# custom_line_V1_mux4.net
KiCad netlist of a schematic drawn in Altium Designer
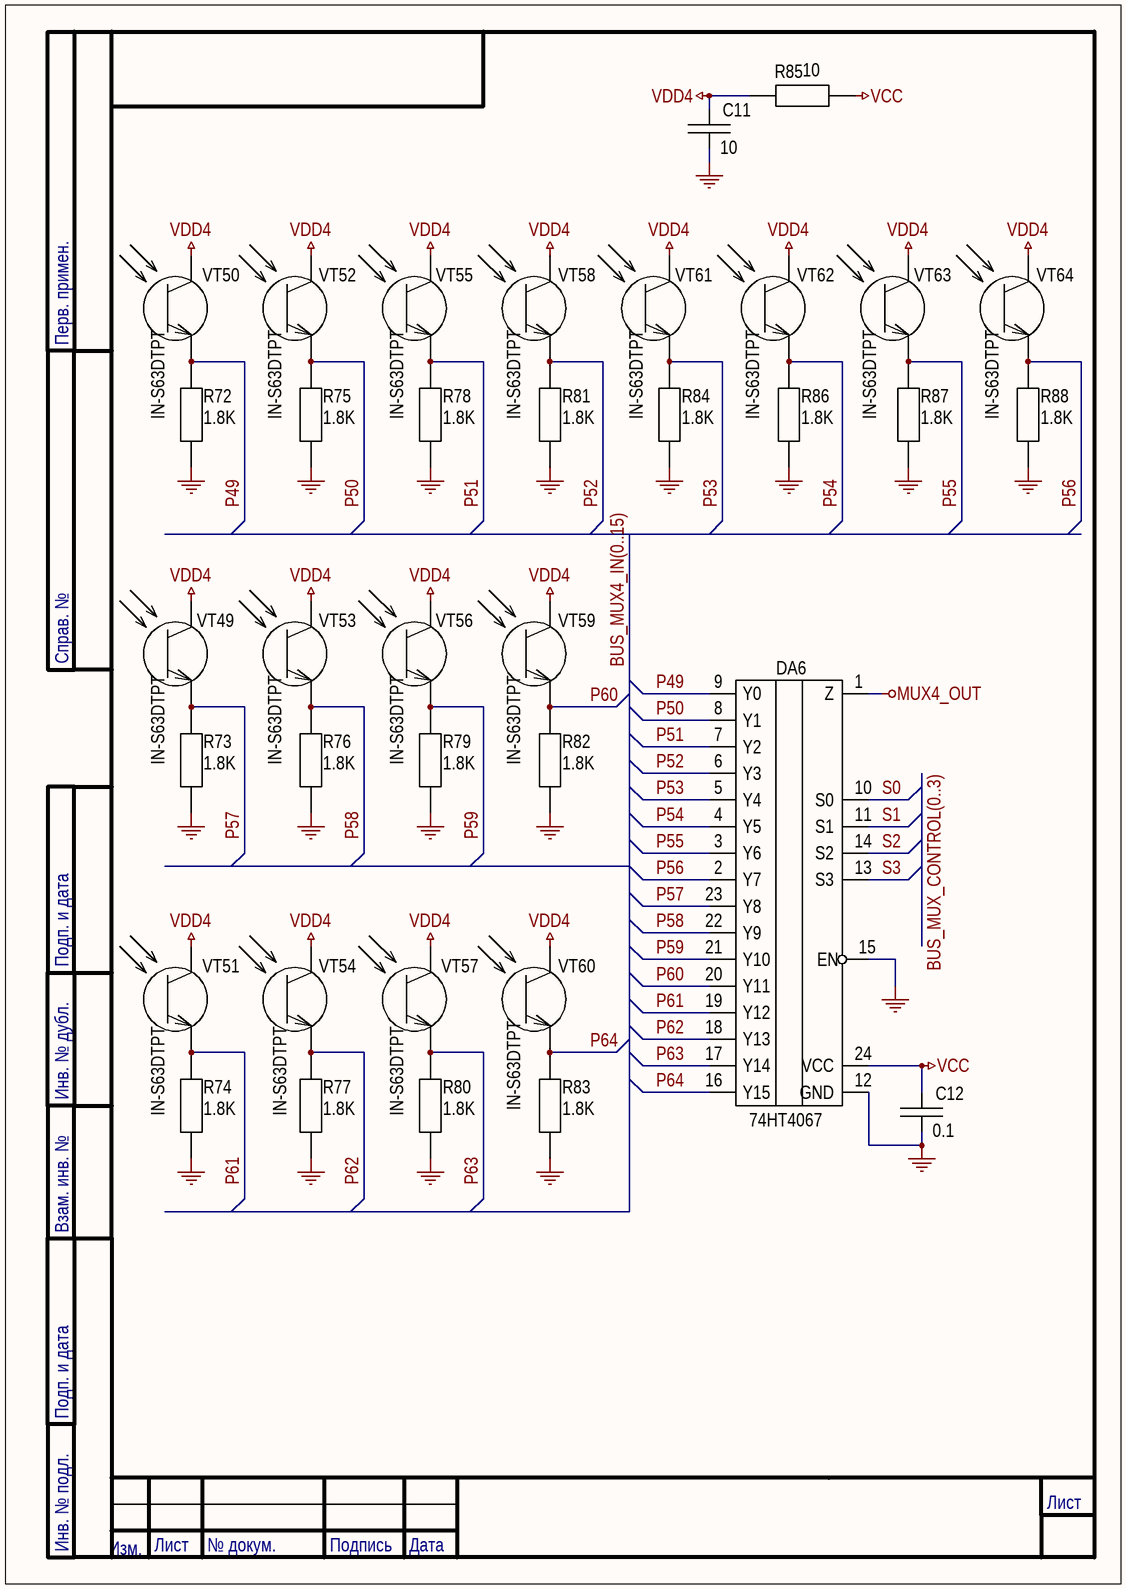
[diagram p0: custom_line_V1_mux4.SchDoc]

(export (version "E")
  (design (tool "Eeschema 10.0.6"))
  (components
    (comp (ref "C11") (value "10") (footprint "CC_0805") (libsource (lib "my_discrete_new") (part "C")))
    (comp (ref "C12") (value "0.1") (footprint "CC_0603") (libsource (lib "my_discrete_new") (part "C")))
    (comp (ref "DA6")
      (value "74HC4067")
      (footprint "TSSOP-24")
      (description "74HC4067PW")
      (fields (field (name "TYPE") "74HT4067"))
      (libsource (lib "my_microschems_new") (part "74HCT4067"))
    )
    (comp (ref "R72")
      (value "1.8K")
      (footprint "RC_0603_SMALL")
      (fields (field (name "POWER") "0.125W"))
      (libsource (lib "my_discrete_new") (part "R"))
    )
    (comp (ref "R73")
      (value "1.8K")
      (footprint "RC_0603_SMALL")
      (fields (field (name "POWER") "0.125W"))
      (libsource (lib "my_discrete_new") (part "R"))
    )
    (comp (ref "R74")
      (value "1.8K")
      (footprint "RC_0603_SMALL")
      (fields (field (name "POWER") "0.125W"))
      (libsource (lib "my_discrete_new") (part "R"))
    )
    (comp (ref "R75")
      (value "1.8K")
      (footprint "RC_0603_SMALL")
      (fields (field (name "POWER") "0.125W"))
      (libsource (lib "my_discrete_new") (part "R"))
    )
    (comp (ref "R76")
      (value "1.8K")
      (footprint "RC_0603_SMALL")
      (fields (field (name "POWER") "0.125W"))
      (libsource (lib "my_discrete_new") (part "R"))
    )
    (comp (ref "R77")
      (value "1.8K")
      (footprint "RC_0603_SMALL")
      (fields (field (name "POWER") "0.125W"))
      (libsource (lib "my_discrete_new") (part "R"))
    )
    (comp (ref "R78")
      (value "1.8K")
      (footprint "RC_0603_SMALL")
      (fields (field (name "POWER") "0.125W"))
      (libsource (lib "my_discrete_new") (part "R"))
    )
    (comp (ref "R79")
      (value "1.8K")
      (footprint "RC_0603_SMALL")
      (fields (field (name "POWER") "0.125W"))
      (libsource (lib "my_discrete_new") (part "R"))
    )
    (comp (ref "R80")
      (value "1.8K")
      (footprint "RC_0603_SMALL")
      (fields (field (name "POWER") "0.125W"))
      (libsource (lib "my_discrete_new") (part "R"))
    )
    (comp (ref "R81")
      (value "1.8K")
      (footprint "RC_0603_SMALL")
      (fields (field (name "POWER") "0.125W"))
      (libsource (lib "my_discrete_new") (part "R"))
    )
    (comp (ref "R82")
      (value "1.8K")
      (footprint "RC_0603_SMALL")
      (fields (field (name "POWER") "0.125W"))
      (libsource (lib "my_discrete_new") (part "R"))
    )
    (comp (ref "R83")
      (value "1.8K")
      (footprint "RC_0603_SMALL")
      (fields (field (name "POWER") "0.125W"))
      (libsource (lib "my_discrete_new") (part "R"))
    )
    (comp (ref "R84")
      (value "1.8K")
      (footprint "RC_0603_SMALL")
      (fields (field (name "POWER") "0.125W"))
      (libsource (lib "my_discrete_new") (part "R"))
    )
    (comp (ref "R85")
      (value "10")
      (footprint "RC_0603_SMALL")
      (fields (field (name "POWER") "0.125W"))
      (libsource (lib "my_discrete_new") (part "R"))
    )
    (comp (ref "R86")
      (value "1.8K")
      (footprint "RC_0603_SMALL")
      (fields (field (name "POWER") "0.125W"))
      (libsource (lib "my_discrete_new") (part "R"))
    )
    (comp (ref "R87")
      (value "1.8K")
      (footprint "RC_0603_SMALL")
      (fields (field (name "POWER") "0.125W"))
      (libsource (lib "my_discrete_new") (part "R"))
    )
    (comp (ref "R88")
      (value "1.8K")
      (footprint "RC_0603_SMALL")
      (fields (field (name "POWER") "0.125W"))
      (libsource (lib "my_discrete_new") (part "R"))
    )
    (comp (ref "VT49")
      (value "IN-S63DTPT")
      (footprint "LED_0603")
      (description "Phototransistor (Inolux)")
      (libsource (lib "my_discrete_new") (part "phototransistor"))
    )
    (comp (ref "VT50")
      (value "IN-S63DTPT")
      (footprint "LED_0603")
      (description "Phototransistor (Inolux)")
      (libsource (lib "my_discrete_new") (part "phototransistor"))
    )
    (comp (ref "VT51")
      (value "IN-S63DTPT")
      (footprint "LED_0603")
      (description "Phototransistor (Inolux)")
      (libsource (lib "my_discrete_new") (part "phototransistor"))
    )
    (comp (ref "VT52")
      (value "IN-S63DTPT")
      (footprint "LED_0603")
      (description "Phototransistor (Inolux)")
      (libsource (lib "my_discrete_new") (part "phototransistor"))
    )
    (comp (ref "VT53")
      (value "IN-S63DTPT")
      (footprint "LED_0603")
      (description "Phototransistor (Inolux)")
      (libsource (lib "my_discrete_new") (part "phototransistor"))
    )
    (comp (ref "VT54")
      (value "IN-S63DTPT")
      (footprint "LED_0603")
      (description "Phototransistor (Inolux)")
      (libsource (lib "my_discrete_new") (part "phototransistor"))
    )
    (comp (ref "VT55")
      (value "IN-S63DTPT")
      (footprint "LED_0603")
      (description "Phototransistor (Inolux)")
      (libsource (lib "my_discrete_new") (part "phototransistor"))
    )
    (comp (ref "VT56")
      (value "IN-S63DTPT")
      (footprint "LED_0603")
      (description "Phototransistor (Inolux)")
      (libsource (lib "my_discrete_new") (part "phototransistor"))
    )
    (comp (ref "VT57")
      (value "IN-S63DTPT")
      (footprint "LED_0603")
      (description "Phototransistor (Inolux)")
      (libsource (lib "my_discrete_new") (part "phototransistor"))
    )
    (comp (ref "VT58")
      (value "IN-S63DTPT")
      (footprint "LED_0603")
      (description "Phototransistor (Inolux)")
      (libsource (lib "my_discrete_new") (part "phototransistor"))
    )
    (comp (ref "VT59")
      (value "IN-S63DTPT")
      (footprint "LED_0603")
      (description "Phototransistor (Inolux)")
      (libsource (lib "my_discrete_new") (part "phototransistor"))
    )
    (comp (ref "VT60")
      (value "IN-S63DTPT")
      (footprint "LED_0603")
      (description "Phototransistor (Inolux)")
      (libsource (lib "my_discrete_new") (part "phototransistor"))
    )
    (comp (ref "VT61")
      (value "IN-S63DTPT")
      (footprint "LED_0603")
      (description "Phototransistor (Inolux)")
      (libsource (lib "my_discrete_new") (part "phototransistor"))
    )
    (comp (ref "VT62")
      (value "IN-S63DTPT")
      (footprint "LED_0603")
      (description "Phototransistor (Inolux)")
      (libsource (lib "my_discrete_new") (part "phototransistor"))
    )
    (comp (ref "VT63")
      (value "IN-S63DTPT")
      (footprint "LED_0603")
      (description "Phototransistor (Inolux)")
      (libsource (lib "my_discrete_new") (part "phototransistor"))
    )
    (comp (ref "VT64")
      (value "IN-S63DTPT")
      (footprint "LED_0603")
      (description "Phototransistor (Inolux)")
      (libsource (lib "my_discrete_new") (part "phototransistor"))
    )
  )
  (nets
    (net (code "3") (name "/P49") (class "Default")
      (node (ref "DA6") (pin "9") (pinfunction "Y0_9") (pintype "passive"))
      (node (ref "R72") (pin "2") (pinfunction "2_2") (pintype "passive"))
      (node (ref "VT50") (pin "2") (pinfunction "E_2") (pintype "passive"))
    )
    (net (code "4") (name "/P50") (class "Default")
      (node (ref "DA6") (pin "8") (pinfunction "Y1_8") (pintype "passive"))
      (node (ref "R75") (pin "2") (pinfunction "2_2") (pintype "passive"))
      (node (ref "VT52") (pin "2") (pinfunction "E_2") (pintype "passive"))
    )
    (net (code "5") (name "/P51") (class "Default")
      (node (ref "DA6") (pin "7") (pinfunction "Y2_7") (pintype "passive"))
      (node (ref "R78") (pin "2") (pinfunction "2_2") (pintype "passive"))
      (node (ref "VT55") (pin "2") (pinfunction "E_2") (pintype "passive"))
    )
    (net (code "6") (name "/P52") (class "Default")
      (node (ref "DA6") (pin "6") (pinfunction "Y3_6") (pintype "passive"))
      (node (ref "R81") (pin "2") (pinfunction "2_2") (pintype "passive"))
      (node (ref "VT58") (pin "2") (pinfunction "E_2") (pintype "passive"))
    )
    (net (code "7") (name "/P53") (class "Default")
      (node (ref "DA6") (pin "5") (pinfunction "Y4_5") (pintype "passive"))
      (node (ref "R84") (pin "2") (pinfunction "2_2") (pintype "passive"))
      (node (ref "VT61") (pin "2") (pinfunction "E_2") (pintype "passive"))
    )
    (net (code "8") (name "/P54") (class "Default")
      (node (ref "DA6") (pin "4") (pinfunction "Y5_4") (pintype "passive"))
      (node (ref "R86") (pin "2") (pinfunction "2_2") (pintype "passive"))
      (node (ref "VT62") (pin "2") (pinfunction "E_2") (pintype "passive"))
    )
    (net (code "9") (name "/P55") (class "Default")
      (node (ref "DA6") (pin "3") (pinfunction "Y6_3") (pintype "passive"))
      (node (ref "R87") (pin "2") (pinfunction "2_2") (pintype "passive"))
      (node (ref "VT63") (pin "2") (pinfunction "E_2") (pintype "passive"))
    )
    (net (code "10") (name "/P56") (class "Default")
      (node (ref "DA6") (pin "2") (pinfunction "Y7_2") (pintype "passive"))
      (node (ref "R88") (pin "2") (pinfunction "2_2") (pintype "passive"))
      (node (ref "VT64") (pin "2") (pinfunction "E_2") (pintype "passive"))
    )
    (net (code "11") (name "/P57") (class "Default")
      (node (ref "DA6") (pin "23") (pinfunction "Y8_23") (pintype "passive"))
      (node (ref "R73") (pin "2") (pinfunction "2_2") (pintype "passive"))
      (node (ref "VT49") (pin "2") (pinfunction "E_2") (pintype "passive"))
    )
    (net (code "12") (name "/P58") (class "Default")
      (node (ref "DA6") (pin "22") (pinfunction "Y9_22") (pintype "passive"))
      (node (ref "R76") (pin "2") (pinfunction "2_2") (pintype "passive"))
      (node (ref "VT53") (pin "2") (pinfunction "E_2") (pintype "passive"))
    )
    (net (code "13") (name "/P59") (class "Default")
      (node (ref "DA6") (pin "21") (pinfunction "Y10_21") (pintype "passive"))
      (node (ref "R79") (pin "2") (pinfunction "2_2") (pintype "passive"))
      (node (ref "VT56") (pin "2") (pinfunction "E_2") (pintype "passive"))
    )
    (net (code "14") (name "/P60") (class "Default")
      (node (ref "DA6") (pin "20") (pinfunction "Y11_20") (pintype "passive"))
      (node (ref "R82") (pin "2") (pinfunction "2_2") (pintype "passive"))
      (node (ref "VT59") (pin "2") (pinfunction "E_2") (pintype "passive"))
    )
    (net (code "15") (name "/P61") (class "Default")
      (node (ref "DA6") (pin "19") (pinfunction "Y12_19") (pintype "passive"))
      (node (ref "R74") (pin "2") (pinfunction "2_2") (pintype "passive"))
      (node (ref "VT51") (pin "2") (pinfunction "E_2") (pintype "passive"))
    )
    (net (code "16") (name "/P62") (class "Default")
      (node (ref "DA6") (pin "18") (pinfunction "Y13_18") (pintype "passive"))
      (node (ref "R77") (pin "2") (pinfunction "2_2") (pintype "passive"))
      (node (ref "VT54") (pin "2") (pinfunction "E_2") (pintype "passive"))
    )
    (net (code "17") (name "/P63") (class "Default")
      (node (ref "DA6") (pin "17") (pinfunction "Y14_17") (pintype "passive"))
      (node (ref "R80") (pin "2") (pinfunction "2_2") (pintype "passive"))
      (node (ref "VT57") (pin "2") (pinfunction "E_2") (pintype "passive"))
    )
    (net (code "18") (name "/P64") (class "Default")
      (node (ref "DA6") (pin "16") (pinfunction "Y15_16") (pintype "passive"))
      (node (ref "R83") (pin "2") (pinfunction "2_2") (pintype "passive"))
      (node (ref "VT60") (pin "2") (pinfunction "E_2") (pintype "passive"))
    )
    (net (code "19") (name "/S0") (class "Default")
      (node (ref "DA6") (pin "10") (pinfunction "S0_10") (pintype "passive"))
    )
    (net (code "20") (name "/S1") (class "Default")
      (node (ref "DA6") (pin "11") (pinfunction "S1_11") (pintype "passive"))
    )
    (net (code "21") (name "/S2") (class "Default")
      (node (ref "DA6") (pin "14") (pinfunction "S2_14") (pintype "passive"))
    )
    (net (code "22") (name "/S3") (class "Default")
      (node (ref "DA6") (pin "13") (pinfunction "S3_13") (pintype "passive"))
    )
    (net (code "25") (name "GND") (class "Default")
      (node (ref "C11") (pin "1") (pinfunction "1_1") (pintype "passive"))
      (node (ref "C12") (pin "1") (pinfunction "1_1") (pintype "passive"))
      (node (ref "DA6") (pin "12") (pinfunction "GND_12") (pintype "power_in"))
      (node (ref "DA6") (pin "15") (pinfunction "EN_15") (pintype "passive"))
      (node (ref "R72") (pin "1") (pinfunction "1_1") (pintype "passive"))
      (node (ref "R73") (pin "1") (pinfunction "1_1") (pintype "passive"))
      (node (ref "R74") (pin "1") (pinfunction "1_1") (pintype "passive"))
      (node (ref "R75") (pin "1") (pinfunction "1_1") (pintype "passive"))
      (node (ref "R76") (pin "1") (pinfunction "1_1") (pintype "passive"))
      (node (ref "R77") (pin "1") (pinfunction "1_1") (pintype "passive"))
      (node (ref "R78") (pin "1") (pinfunction "1_1") (pintype "passive"))
      (node (ref "R79") (pin "1") (pinfunction "1_1") (pintype "passive"))
      (node (ref "R80") (pin "1") (pinfunction "1_1") (pintype "passive"))
      (node (ref "R81") (pin "1") (pinfunction "1_1") (pintype "passive"))
      (node (ref "R82") (pin "1") (pinfunction "1_1") (pintype "passive"))
      (node (ref "R83") (pin "1") (pinfunction "1_1") (pintype "passive"))
      (node (ref "R84") (pin "1") (pinfunction "1_1") (pintype "passive"))
      (node (ref "R86") (pin "1") (pinfunction "1_1") (pintype "passive"))
      (node (ref "R87") (pin "1") (pinfunction "1_1") (pintype "passive"))
      (node (ref "R88") (pin "1") (pinfunction "1_1") (pintype "passive"))
    )
    (net (code "26") (name "MUX4_OUT") (class "Default")
      (node (ref "DA6") (pin "1") (pinfunction "Z_1") (pintype "passive"))
    )
    (net (code "27") (name "VCC") (class "Default")
      (node (ref "C12") (pin "2") (pinfunction "2_2") (pintype "passive"))
      (node (ref "DA6") (pin "24") (pinfunction "VCC_24") (pintype "power_in"))
      (node (ref "R85") (pin "1") (pinfunction "1_1") (pintype "passive"))
    )
    (net (code "28") (name "VDD4") (class "Default")
      (node (ref "C11") (pin "2") (pinfunction "2_2") (pintype "passive"))
      (node (ref "R85") (pin "2") (pinfunction "2_2") (pintype "passive"))
      (node (ref "VT49") (pin "1") (pinfunction "C_1") (pintype "passive"))
      (node (ref "VT50") (pin "1") (pinfunction "C_1") (pintype "passive"))
      (node (ref "VT51") (pin "1") (pinfunction "C_1") (pintype "passive"))
      (node (ref "VT52") (pin "1") (pinfunction "C_1") (pintype "passive"))
      (node (ref "VT53") (pin "1") (pinfunction "C_1") (pintype "passive"))
      (node (ref "VT54") (pin "1") (pinfunction "C_1") (pintype "passive"))
      (node (ref "VT55") (pin "1") (pinfunction "C_1") (pintype "passive"))
      (node (ref "VT56") (pin "1") (pinfunction "C_1") (pintype "passive"))
      (node (ref "VT57") (pin "1") (pinfunction "C_1") (pintype "passive"))
      (node (ref "VT58") (pin "1") (pinfunction "C_1") (pintype "passive"))
      (node (ref "VT59") (pin "1") (pinfunction "C_1") (pintype "passive"))
      (node (ref "VT60") (pin "1") (pinfunction "C_1") (pintype "passive"))
      (node (ref "VT61") (pin "1") (pinfunction "C_1") (pintype "passive"))
      (node (ref "VT62") (pin "1") (pinfunction "C_1") (pintype "passive"))
      (node (ref "VT63") (pin "1") (pinfunction "C_1") (pintype "passive"))
      (node (ref "VT64") (pin "1") (pinfunction "C_1") (pintype "passive"))
    )
  )
)
